# universal_opamp_circuit_REV1.net
KiCad netlist of a schematic drawn in EAGLE
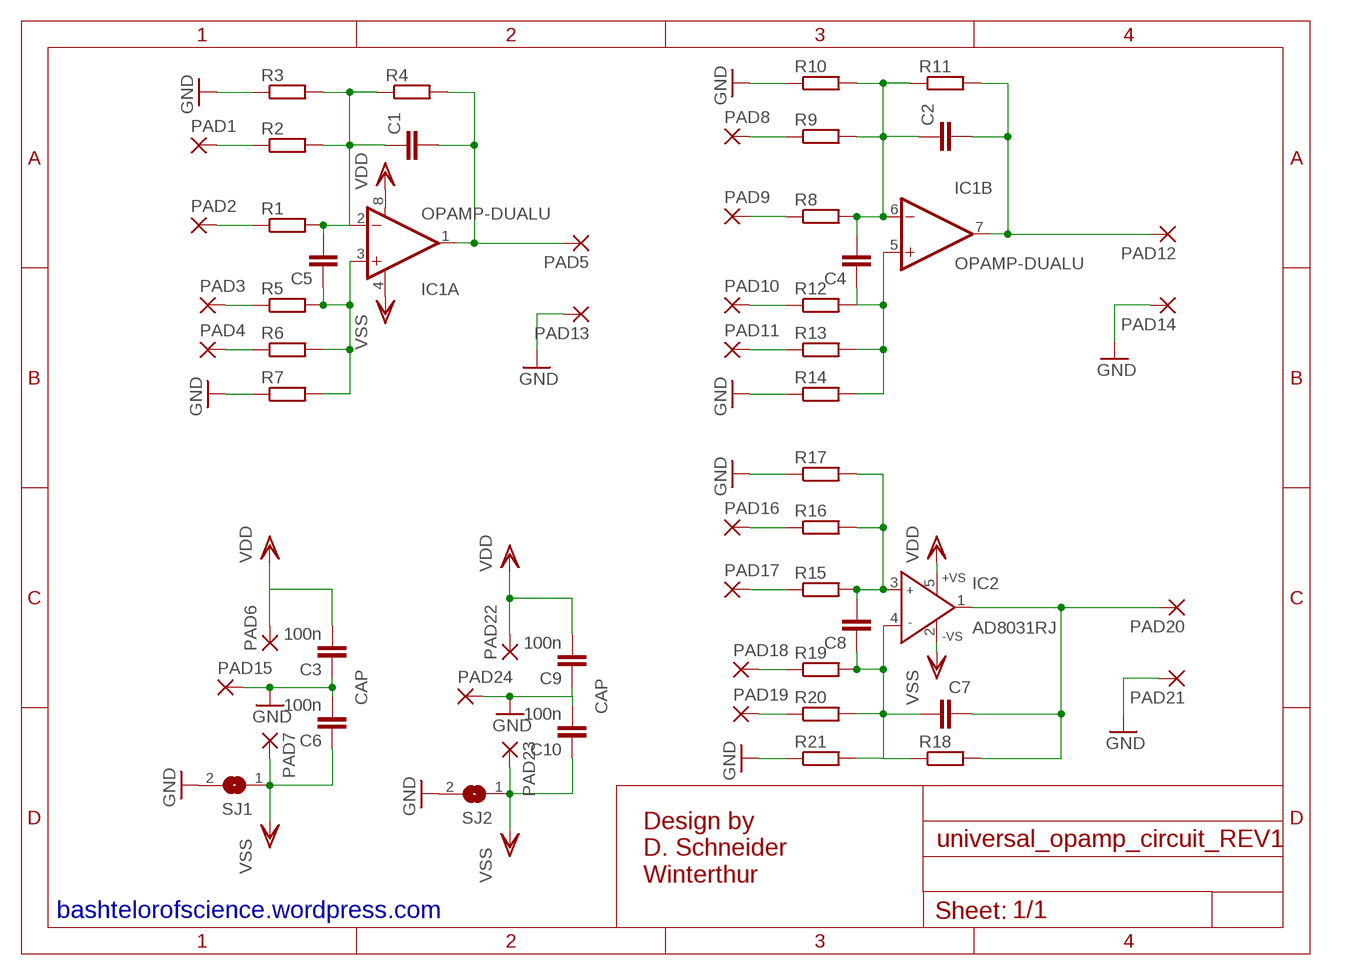
[diagram p0: schematic, sheet 1]

(export (version "E")
  (design (tool "Eeschema 10.0.6"))
  (components
    (comp (ref "C1")
      (value "C-EUC0603")
      (footprint "eagle-import:C0603")
      (libsource (lib "eagle-import") (part "C-EUC0603"))
    )
    (comp (ref "C2")
      (value "C-EUC0603")
      (footprint "eagle-import:C0603")
      (libsource (lib "eagle-import") (part "C-EUC0603"))
    )
    (comp (ref "C3")
      (value "100n")
      (footprint "eagle-import:C0603")
      (libsource (lib "eagle-import") (part "C-EUC0603"))
    )
    (comp (ref "C4")
      (value "C-EUC0603")
      (footprint "eagle-import:C0603")
      (libsource (lib "eagle-import") (part "C-EUC0603"))
    )
    (comp (ref "C5")
      (value "C-EUC0603")
      (footprint "eagle-import:C0603")
      (libsource (lib "eagle-import") (part "C-EUC0603"))
    )
    (comp (ref "C6")
      (value "100n")
      (footprint "eagle-import:C0603")
      (libsource (lib "eagle-import") (part "C-EUC0603"))
    )
    (comp (ref "C7")
      (value "C-EUC0603")
      (footprint "eagle-import:C0603")
      (libsource (lib "eagle-import") (part "C-EUC0603"))
    )
    (comp (ref "C8")
      (value "C-EUC0603")
      (footprint "eagle-import:C0603")
      (libsource (lib "eagle-import") (part "C-EUC0603"))
    )
    (comp (ref "C9")
      (value "100n")
      (footprint "eagle-import:C0603")
      (libsource (lib "eagle-import") (part "C-EUC0603"))
    )
    (comp (ref "C10")
      (value "100n")
      (footprint "eagle-import:C0603")
      (libsource (lib "eagle-import") (part "C-EUC0603"))
    )
    (comp (ref "IC1")
      (value "OPAMP-DUALU")
      (footprint "eagle-import:SO08")
      (libsource (lib "eagle-import") (part "OPAMP-DUALU"))
    )
    (comp (ref "IC2")
      (value "AD8031RJ")
      (footprint "eagle-import:SOT23-5")
      (fields (field (name "MPN") "AD8031ARTZ-REEL7"))
      (libsource (lib "eagle-import") (part "AD8031RJ"))
    )
    (comp (ref "PAD1")
      (value "1,6/0,9")
      (footprint "eagle-import:1,6_0,9")
      (libsource (lib "eagle-import") (part "1,6/0,9"))
    )
    (comp (ref "PAD2")
      (value "1,6/0,9")
      (footprint "eagle-import:1,6_0,9")
      (libsource (lib "eagle-import") (part "1,6/0,9"))
    )
    (comp (ref "PAD3")
      (value "1,6/0,9")
      (footprint "eagle-import:1,6_0,9")
      (libsource (lib "eagle-import") (part "1,6/0,9"))
    )
    (comp (ref "PAD4")
      (value "1,6/0,9")
      (footprint "eagle-import:1,6_0,9")
      (libsource (lib "eagle-import") (part "1,6/0,9"))
    )
    (comp (ref "PAD5")
      (value "1,6/0,9")
      (footprint "eagle-import:1,6_0,9")
      (libsource (lib "eagle-import") (part "1,6/0,9"))
    )
    (comp (ref "PAD6")
      (value "1,6/0,9")
      (footprint "eagle-import:1,6_0,9")
      (libsource (lib "eagle-import") (part "1,6/0,9"))
    )
    (comp (ref "PAD7")
      (value "1,6/0,9")
      (footprint "eagle-import:1,6_0,9")
      (libsource (lib "eagle-import") (part "1,6/0,9"))
    )
    (comp (ref "PAD8")
      (value "1,6/0,9")
      (footprint "eagle-import:1,6_0,9")
      (libsource (lib "eagle-import") (part "1,6/0,9"))
    )
    (comp (ref "PAD9")
      (value "1,6/0,9")
      (footprint "eagle-import:1,6_0,9")
      (libsource (lib "eagle-import") (part "1,6/0,9"))
    )
    (comp (ref "PAD10")
      (value "1,6/0,9")
      (footprint "eagle-import:1,6_0,9")
      (libsource (lib "eagle-import") (part "1,6/0,9"))
    )
    (comp (ref "PAD11")
      (value "1,6/0,9")
      (footprint "eagle-import:1,6_0,9")
      (libsource (lib "eagle-import") (part "1,6/0,9"))
    )
    (comp (ref "PAD12")
      (value "1,6/0,9")
      (footprint "eagle-import:1,6_0,9")
      (libsource (lib "eagle-import") (part "1,6/0,9"))
    )
    (comp (ref "PAD13")
      (value "1,6/0,9")
      (footprint "eagle-import:1,6_0,9")
      (libsource (lib "eagle-import") (part "1,6/0,9"))
    )
    (comp (ref "PAD14")
      (value "1,6/0,9")
      (footprint "eagle-import:1,6_0,9")
      (libsource (lib "eagle-import") (part "1,6/0,9"))
    )
    (comp (ref "PAD15")
      (value "1,6/0,9")
      (footprint "eagle-import:1,6_0,9")
      (libsource (lib "eagle-import") (part "1,6/0,9"))
    )
    (comp (ref "PAD16")
      (value "1,6/0,9")
      (footprint "eagle-import:1,6_0,9")
      (libsource (lib "eagle-import") (part "1,6/0,9"))
    )
    (comp (ref "PAD17")
      (value "1,6/0,9")
      (footprint "eagle-import:1,6_0,9")
      (libsource (lib "eagle-import") (part "1,6/0,9"))
    )
    (comp (ref "PAD18")
      (value "1,6/0,9")
      (footprint "eagle-import:1,6_0,9")
      (libsource (lib "eagle-import") (part "1,6/0,9"))
    )
    (comp (ref "PAD19")
      (value "1,6/0,9")
      (footprint "eagle-import:1,6_0,9")
      (libsource (lib "eagle-import") (part "1,6/0,9"))
    )
    (comp (ref "PAD20")
      (value "1,6/0,9")
      (footprint "eagle-import:1,6_0,9")
      (libsource (lib "eagle-import") (part "1,6/0,9"))
    )
    (comp (ref "PAD21")
      (value "1,6/0,9")
      (footprint "eagle-import:1,6_0,9")
      (libsource (lib "eagle-import") (part "1,6/0,9"))
    )
    (comp (ref "PAD22")
      (value "1,6/0,9")
      (footprint "eagle-import:1,6_0,9")
      (libsource (lib "eagle-import") (part "1,6/0,9"))
    )
    (comp (ref "PAD23")
      (value "1,6/0,9")
      (footprint "eagle-import:1,6_0,9")
      (libsource (lib "eagle-import") (part "1,6/0,9"))
    )
    (comp (ref "PAD24")
      (value "1,6/0,9")
      (footprint "eagle-import:1,6_0,9")
      (libsource (lib "eagle-import") (part "1,6/0,9"))
    )
    (comp (ref "R1")
      (value "R-EU_R0603")
      (footprint "eagle-import:R0603")
      (libsource (lib "eagle-import") (part "R-EU_R0603"))
    )
    (comp (ref "R2")
      (value "R-EU_R0603")
      (footprint "eagle-import:R0603")
      (libsource (lib "eagle-import") (part "R-EU_R0603"))
    )
    (comp (ref "R3")
      (value "R-EU_R0603")
      (footprint "eagle-import:R0603")
      (libsource (lib "eagle-import") (part "R-EU_R0603"))
    )
    (comp (ref "R4")
      (value "R-EU_R0603")
      (footprint "eagle-import:R0603")
      (libsource (lib "eagle-import") (part "R-EU_R0603"))
    )
    (comp (ref "R5")
      (value "R-EU_R0603")
      (footprint "eagle-import:R0603")
      (libsource (lib "eagle-import") (part "R-EU_R0603"))
    )
    (comp (ref "R6")
      (value "R-EU_R0603")
      (footprint "eagle-import:R0603")
      (libsource (lib "eagle-import") (part "R-EU_R0603"))
    )
    (comp (ref "R7")
      (value "R-EU_R0603")
      (footprint "eagle-import:R0603")
      (libsource (lib "eagle-import") (part "R-EU_R0603"))
    )
    (comp (ref "R8")
      (value "R-EU_R0603")
      (footprint "eagle-import:R0603")
      (libsource (lib "eagle-import") (part "R-EU_R0603"))
    )
    (comp (ref "R9")
      (value "R-EU_R0603")
      (footprint "eagle-import:R0603")
      (libsource (lib "eagle-import") (part "R-EU_R0603"))
    )
    (comp (ref "R10")
      (value "R-EU_R0603")
      (footprint "eagle-import:R0603")
      (libsource (lib "eagle-import") (part "R-EU_R0603"))
    )
    (comp (ref "R11")
      (value "R-EU_R0603")
      (footprint "eagle-import:R0603")
      (libsource (lib "eagle-import") (part "R-EU_R0603"))
    )
    (comp (ref "R12")
      (value "R-EU_R0603")
      (footprint "eagle-import:R0603")
      (libsource (lib "eagle-import") (part "R-EU_R0603"))
    )
    (comp (ref "R13")
      (value "R-EU_R0603")
      (footprint "eagle-import:R0603")
      (libsource (lib "eagle-import") (part "R-EU_R0603"))
    )
    (comp (ref "R14")
      (value "R-EU_R0603")
      (footprint "eagle-import:R0603")
      (libsource (lib "eagle-import") (part "R-EU_R0603"))
    )
    (comp (ref "R15")
      (value "R-EU_R0603")
      (footprint "eagle-import:R0603")
      (libsource (lib "eagle-import") (part "R-EU_R0603"))
    )
    (comp (ref "R16")
      (value "R-EU_R0603")
      (footprint "eagle-import:R0603")
      (libsource (lib "eagle-import") (part "R-EU_R0603"))
    )
    (comp (ref "R17")
      (value "R-EU_R0603")
      (footprint "eagle-import:R0603")
      (libsource (lib "eagle-import") (part "R-EU_R0603"))
    )
    (comp (ref "R18")
      (value "R-EU_R0603")
      (footprint "eagle-import:R0603")
      (libsource (lib "eagle-import") (part "R-EU_R0603"))
    )
    (comp (ref "R19")
      (value "R-EU_R0603")
      (footprint "eagle-import:R0603")
      (libsource (lib "eagle-import") (part "R-EU_R0603"))
    )
    (comp (ref "R20")
      (value "R-EU_R0603")
      (footprint "eagle-import:R0603")
      (libsource (lib "eagle-import") (part "R-EU_R0603"))
    )
    (comp (ref "R21")
      (value "R-EU_R0603")
      (footprint "eagle-import:R0603")
      (libsource (lib "eagle-import") (part "R-EU_R0603"))
    )
    (comp (ref "SJ1") (value "SJ") (footprint "eagle-import:SJ") (libsource (lib "eagle-import") (part "SJ")))
    (comp (ref "SJ2") (value "SJ") (footprint "eagle-import:SJ") (libsource (lib "eagle-import") (part "SJ")))
  )
  (nets
    (net (code "1") (name "GND") (class "Default")
      (node (ref "C10") (pin "2") (pinfunction "2_2") (pintype "passive"))
      (node (ref "C3") (pin "1") (pinfunction "1_1") (pintype "passive"))
      (node (ref "C6") (pin "2") (pinfunction "2_2") (pintype "passive"))
      (node (ref "C9") (pin "1") (pinfunction "1_1") (pintype "passive"))
      (node (ref "PAD13") (pin "1") (pinfunction "P_1") (pintype "passive"))
      (node (ref "PAD14") (pin "1") (pinfunction "P_1") (pintype "passive"))
      (node (ref "PAD15") (pin "1") (pinfunction "P_1") (pintype "passive"))
      (node (ref "PAD21") (pin "1") (pinfunction "P_1") (pintype "passive"))
      (node (ref "PAD24") (pin "1") (pinfunction "P_1") (pintype "passive"))
      (node (ref "R10") (pin "1") (pinfunction "1_1") (pintype "passive"))
      (node (ref "R14") (pin "1") (pinfunction "1_1") (pintype "passive"))
      (node (ref "R17") (pin "1") (pinfunction "1_1") (pintype "passive"))
      (node (ref "R21") (pin "1") (pinfunction "1_1") (pintype "passive"))
      (node (ref "R3") (pin "1") (pinfunction "1_1") (pintype "passive"))
      (node (ref "R7") (pin "1") (pinfunction "1_1") (pintype "passive"))
      (node (ref "SJ1") (pin "2") (pinfunction "2_2") (pintype "passive"))
      (node (ref "SJ2") (pin "2") (pinfunction "2_2") (pintype "passive"))
    )
    (net (code "2") (name "Net-(IC1A-+IN)") (class "Default")
      (node (ref "C5") (pin "1") (pinfunction "1_1") (pintype "passive"))
      (node (ref "IC1") (pin "3") (pinfunction "+IN_3") (pintype "input"))
      (node (ref "R5") (pin "2") (pinfunction "2_2") (pintype "passive"))
      (node (ref "R6") (pin "2") (pinfunction "2_2") (pintype "passive"))
      (node (ref "R7") (pin "2") (pinfunction "2_2") (pintype "passive"))
    )
    (net (code "3") (name "Net-(IC1A--IN)") (class "Default")
      (node (ref "C1") (pin "1") (pinfunction "1_1") (pintype "passive"))
      (node (ref "C5") (pin "2") (pinfunction "2_2") (pintype "passive"))
      (node (ref "IC1") (pin "2") (pinfunction "-IN_2") (pintype "input"))
      (node (ref "R1") (pin "2") (pinfunction "2_2") (pintype "passive"))
      (node (ref "R2") (pin "2") (pinfunction "2_2") (pintype "passive"))
      (node (ref "R3") (pin "2") (pinfunction "2_2") (pintype "passive"))
      (node (ref "R4") (pin "1") (pinfunction "1_1") (pintype "passive"))
    )
    (net (code "4") (name "Net-(IC1A-OUT)") (class "Default")
      (node (ref "C1") (pin "2") (pinfunction "2_2") (pintype "passive"))
      (node (ref "IC1") (pin "1") (pinfunction "OUT_1") (pintype "output"))
      (node (ref "PAD5") (pin "1") (pinfunction "P_1") (pintype "passive"))
      (node (ref "R4") (pin "2") (pinfunction "2_2") (pintype "passive"))
    )
    (net (code "5") (name "Net-(IC1B-+IN)") (class "Default")
      (node (ref "C4") (pin "1") (pinfunction "1_1") (pintype "passive"))
      (node (ref "IC1") (pin "5") (pinfunction "+IN_5") (pintype "input"))
      (node (ref "R12") (pin "2") (pinfunction "2_2") (pintype "passive"))
      (node (ref "R13") (pin "2") (pinfunction "2_2") (pintype "passive"))
      (node (ref "R14") (pin "2") (pinfunction "2_2") (pintype "passive"))
    )
    (net (code "6") (name "Net-(IC1B--IN)") (class "Default")
      (node (ref "C2") (pin "1") (pinfunction "1_1") (pintype "passive"))
      (node (ref "C4") (pin "2") (pinfunction "2_2") (pintype "passive"))
      (node (ref "IC1") (pin "6") (pinfunction "-IN_6") (pintype "input"))
      (node (ref "R10") (pin "2") (pinfunction "2_2") (pintype "passive"))
      (node (ref "R11") (pin "1") (pinfunction "1_1") (pintype "passive"))
      (node (ref "R8") (pin "2") (pinfunction "2_2") (pintype "passive"))
      (node (ref "R9") (pin "2") (pinfunction "2_2") (pintype "passive"))
    )
    (net (code "7") (name "Net-(IC1B-OUT)") (class "Default")
      (node (ref "C2") (pin "2") (pinfunction "2_2") (pintype "passive"))
      (node (ref "IC1") (pin "7") (pinfunction "OUT_7") (pintype "output"))
      (node (ref "PAD12") (pin "1") (pinfunction "P_1") (pintype "passive"))
      (node (ref "R11") (pin "2") (pinfunction "2_2") (pintype "passive"))
    )
    (net (code "8") (name "Net-(IC2-IN+)") (class "Default")
      (node (ref "C8") (pin "2") (pinfunction "2_2") (pintype "passive"))
      (node (ref "IC2") (pin "3") (pinfunction "IN+_3") (pintype "input"))
      (node (ref "R15") (pin "2") (pinfunction "2_2") (pintype "passive"))
      (node (ref "R16") (pin "2") (pinfunction "2_2") (pintype "passive"))
      (node (ref "R17") (pin "2") (pinfunction "2_2") (pintype "passive"))
    )
    (net (code "9") (name "Net-(IC2-IN-)") (class "Default")
      (node (ref "C7") (pin "1") (pinfunction "1_1") (pintype "passive"))
      (node (ref "C8") (pin "1") (pinfunction "1_1") (pintype "passive"))
      (node (ref "IC2") (pin "4") (pinfunction "IN-_4") (pintype "input"))
      (node (ref "R18") (pin "1") (pinfunction "1_1") (pintype "passive"))
      (node (ref "R19") (pin "2") (pinfunction "2_2") (pintype "passive"))
      (node (ref "R20") (pin "2") (pinfunction "2_2") (pintype "passive"))
      (node (ref "R21") (pin "2") (pinfunction "2_2") (pintype "passive"))
    )
    (net (code "10") (name "Net-(IC2-OUT)") (class "Default")
      (node (ref "C7") (pin "2") (pinfunction "2_2") (pintype "passive"))
      (node (ref "IC2") (pin "1") (pinfunction "OUT_1") (pintype "output"))
      (node (ref "PAD20") (pin "1") (pinfunction "P_1") (pintype "passive"))
      (node (ref "R18") (pin "2") (pinfunction "2_2") (pintype "passive"))
    )
    (net (code "11") (name "Net-(PAD1-P)") (class "Default")
      (node (ref "PAD1") (pin "1") (pinfunction "P_1") (pintype "passive"))
      (node (ref "R2") (pin "1") (pinfunction "1_1") (pintype "passive"))
    )
    (net (code "12") (name "Net-(PAD2-P)") (class "Default")
      (node (ref "PAD2") (pin "1") (pinfunction "P_1") (pintype "passive"))
      (node (ref "R1") (pin "1") (pinfunction "1_1") (pintype "passive"))
    )
    (net (code "13") (name "Net-(PAD3-P)") (class "Default")
      (node (ref "PAD3") (pin "1") (pinfunction "P_1") (pintype "passive"))
      (node (ref "R5") (pin "1") (pinfunction "1_1") (pintype "passive"))
    )
    (net (code "14") (name "Net-(PAD4-P)") (class "Default")
      (node (ref "PAD4") (pin "1") (pinfunction "P_1") (pintype "passive"))
      (node (ref "R6") (pin "1") (pinfunction "1_1") (pintype "passive"))
    )
    (net (code "15") (name "Net-(PAD8-P)") (class "Default")
      (node (ref "PAD8") (pin "1") (pinfunction "P_1") (pintype "passive"))
      (node (ref "R9") (pin "1") (pinfunction "1_1") (pintype "passive"))
    )
    (net (code "16") (name "Net-(PAD9-P)") (class "Default")
      (node (ref "PAD9") (pin "1") (pinfunction "P_1") (pintype "passive"))
      (node (ref "R8") (pin "1") (pinfunction "1_1") (pintype "passive"))
    )
    (net (code "17") (name "Net-(PAD10-P)") (class "Default")
      (node (ref "PAD10") (pin "1") (pinfunction "P_1") (pintype "passive"))
      (node (ref "R12") (pin "1") (pinfunction "1_1") (pintype "passive"))
    )
    (net (code "18") (name "Net-(PAD11-P)") (class "Default")
      (node (ref "PAD11") (pin "1") (pinfunction "P_1") (pintype "passive"))
      (node (ref "R13") (pin "1") (pinfunction "1_1") (pintype "passive"))
    )
    (net (code "19") (name "Net-(PAD16-P)") (class "Default")
      (node (ref "PAD16") (pin "1") (pinfunction "P_1") (pintype "passive"))
      (node (ref "R16") (pin "1") (pinfunction "1_1") (pintype "passive"))
    )
    (net (code "20") (name "Net-(PAD17-P)") (class "Default")
      (node (ref "PAD17") (pin "1") (pinfunction "P_1") (pintype "passive"))
      (node (ref "R15") (pin "1") (pinfunction "1_1") (pintype "passive"))
    )
    (net (code "21") (name "Net-(PAD18-P)") (class "Default")
      (node (ref "PAD18") (pin "1") (pinfunction "P_1") (pintype "passive"))
      (node (ref "R19") (pin "1") (pinfunction "1_1") (pintype "passive"))
    )
    (net (code "22") (name "Net-(PAD19-P)") (class "Default")
      (node (ref "PAD19") (pin "1") (pinfunction "P_1") (pintype "passive"))
      (node (ref "R20") (pin "1") (pinfunction "1_1") (pintype "passive"))
    )
    (net (code "23") (name "VDD") (class "Default")
      (node (ref "C3") (pin "2") (pinfunction "2_2") (pintype "passive"))
      (node (ref "C9") (pin "2") (pinfunction "2_2") (pintype "passive"))
      (node (ref "IC1") (pin "8") (pinfunction "V+_8") (pintype "power_in"))
      (node (ref "IC2") (pin "5") (pinfunction "+VS_5") (pintype "input"))
      (node (ref "PAD22") (pin "1") (pinfunction "P_1") (pintype "passive"))
      (node (ref "PAD6") (pin "1") (pinfunction "P_1") (pintype "passive"))
    )
    (net (code "24") (name "VSS") (class "Default")
      (node (ref "C10") (pin "1") (pinfunction "1_1") (pintype "passive"))
      (node (ref "C6") (pin "1") (pinfunction "1_1") (pintype "passive"))
      (node (ref "IC1") (pin "4") (pinfunction "V-_4") (pintype "power_in"))
      (node (ref "IC2") (pin "2") (pinfunction "-VS_2") (pintype "input"))
      (node (ref "PAD23") (pin "1") (pinfunction "P_1") (pintype "passive"))
      (node (ref "PAD7") (pin "1") (pinfunction "P_1") (pintype "passive"))
      (node (ref "SJ1") (pin "1") (pinfunction "1_1") (pintype "passive"))
      (node (ref "SJ2") (pin "1") (pinfunction "1_1") (pintype "passive"))
    )
  )
)
